# SCH_skymest-2026_06_07_2026-06-14.net
KiCad netlist of a schematic drawn in EasyEDA
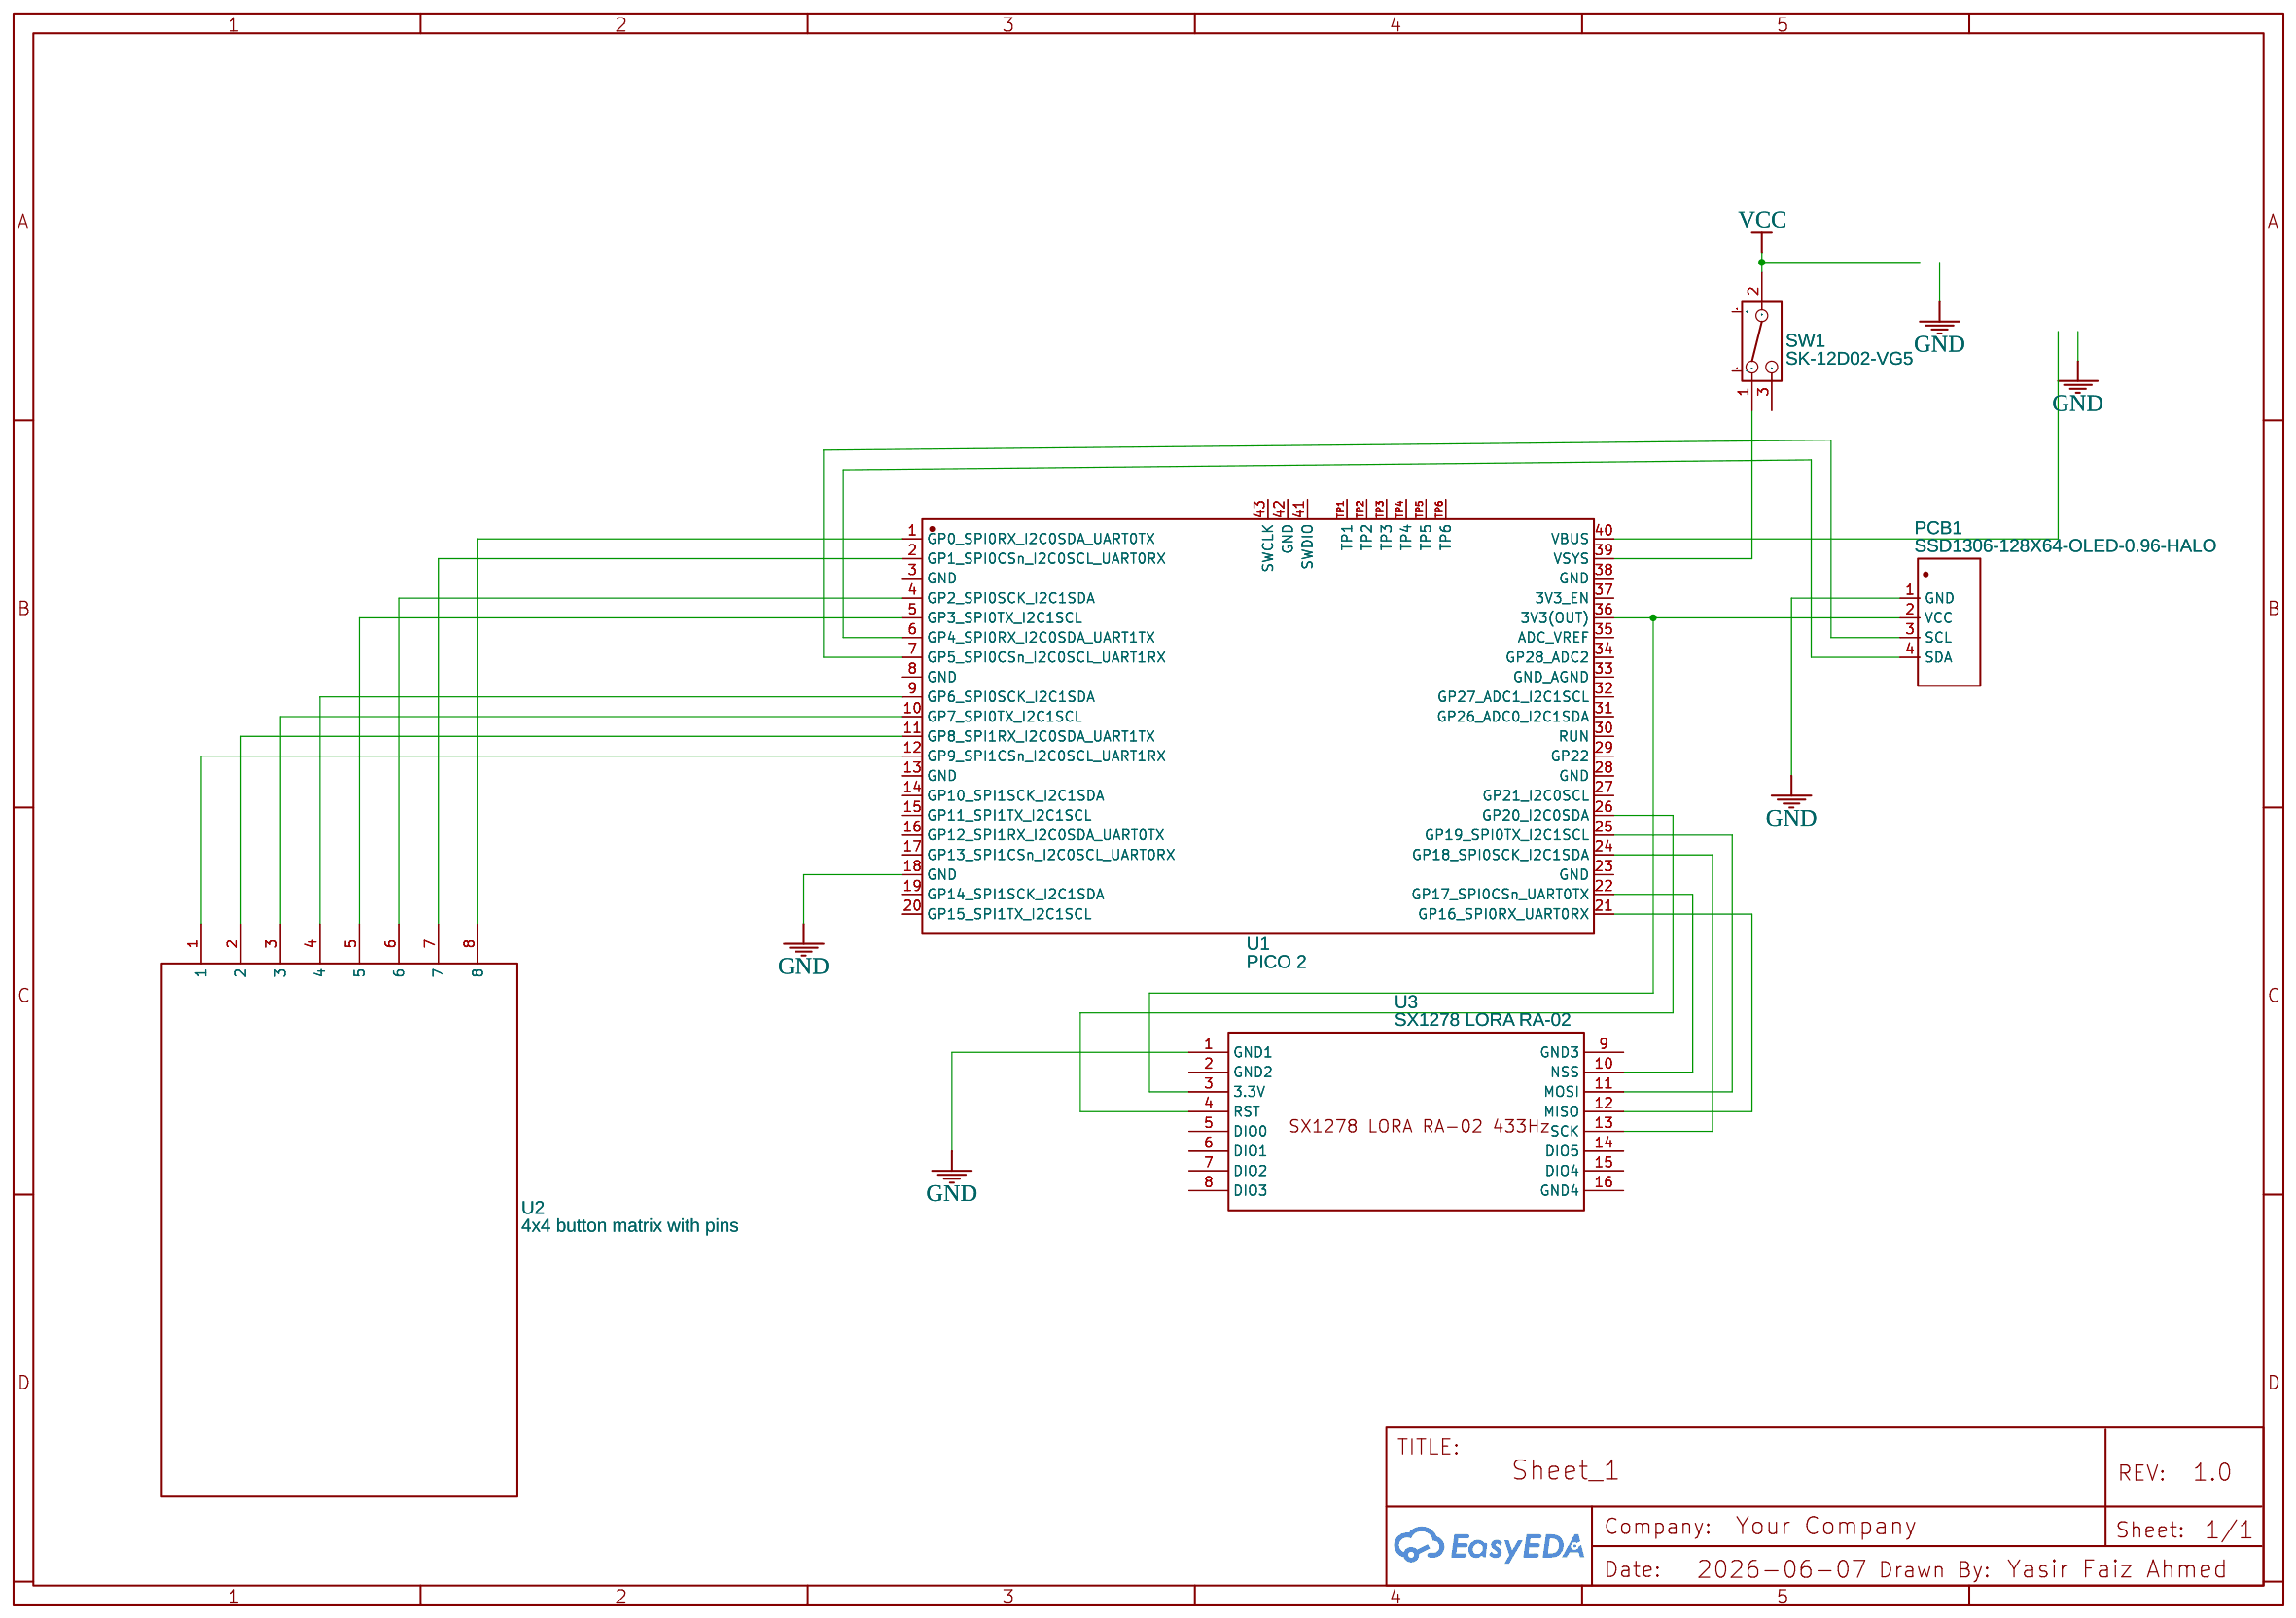
[diagram p0: schematic sheet]

(export (version "E")
  (design (tool "Eeschema 10.0.6"))
  (components
    (comp (ref "PCB1")
      (value "SSD1306-128X64-OLED-0.96-HALO")
      (libsource (lib "") (part "SSD1306-128X64-OLED-0.96-HALO"))
    )
    (comp (ref "SW1")
      (value "SK-12D02-VG5")
      (fields (field (name "Manufacturer") "Rectangular Connectors - Contacts"))
      (libsource (lib "") (part "SK-12D02-VG5"))
    )
    (comp (ref "U1")
      (value "PICO 2")
      (fields (field (name "Manufacturer Part") "Pico 2") (field (name "Manufacturer") "Raspberry Pi(树莓派)"))
      (libsource (lib "") (part "PICO 2"))
    )
    (comp (ref "U2")
      (value "4x4 button matrix with pins")
      (libsource (lib "") (part "4x4 button matrix with pins"))
    )
    (comp (ref "U3") (value "SX1278 LORA RA-02") (libsource (lib "") (part "SX1278 LORA RA-02")))
  )
  (nets
    (net (code "1") (name "GND") (class "Default")
      (node (ref "PCB1") (pin "1") (pinfunction "GND_1") (pintype "input"))
      (node (ref "U1") (pin "18") (pinfunction "GND_18") (pintype "unspecified"))
      (node (ref "U3") (pin "1") (pinfunction "GND1_1") (pintype "unspecified"))
    )
    (net (code "2") (name "Net-(PCB1-SCL)") (class "Default")
      (node (ref "PCB1") (pin "3") (pinfunction "SCL_3") (pintype "passive"))
      (node (ref "U1") (pin "7") (pinfunction "GP5_SPI0CSn_I2C0SCL_UART1RX_7") (pintype "unspecified"))
    )
    (net (code "3") (name "Net-(PCB1-SDA)") (class "Default")
      (node (ref "PCB1") (pin "4") (pinfunction "SDA_4") (pintype "passive"))
      (node (ref "U1") (pin "6") (pinfunction "GP4_SPI0RX_I2C0SDA_UART1TX_6") (pintype "unspecified"))
    )
    (net (code "4") (name "Net-(PCB1-VCC)") (class "Default")
      (node (ref "PCB1") (pin "2") (pinfunction "VCC_2") (pintype "input"))
      (node (ref "U1") (pin "36") (pinfunction "3V3(OUT)_36") (pintype "unspecified"))
      (node (ref "U3") (pin "3") (pinfunction "3.3V_3") (pintype "unspecified"))
    )
    (net (code "5") (name "Net-(U1-GP0_SPI0RX_I2C0SDA_UART0TX)") (class "Default")
      (node (ref "U1") (pin "1") (pinfunction "GP0_SPI0RX_I2C0SDA_UART0TX_1") (pintype "unspecified"))
      (node (ref "U2") (pin "8") (pinfunction "8_8") (pintype "unspecified"))
    )
    (net (code "6") (name "Net-(U1-GP1_SPI0CSn_I2C0SCL_UART0RX)") (class "Default")
      (node (ref "U1") (pin "2") (pinfunction "GP1_SPI0CSn_I2C0SCL_UART0RX_2") (pintype "unspecified"))
      (node (ref "U2") (pin "7") (pinfunction "7_7") (pintype "unspecified"))
    )
    (net (code "7") (name "Net-(U1-GP2_SPI0SCK_I2C1SDA)") (class "Default")
      (node (ref "U1") (pin "4") (pinfunction "GP2_SPI0SCK_I2C1SDA_4") (pintype "unspecified"))
      (node (ref "U2") (pin "6") (pinfunction "6_6") (pintype "unspecified"))
    )
    (net (code "8") (name "Net-(U1-GP3_SPI0TX_I2C1SCL)") (class "Default")
      (node (ref "U1") (pin "5") (pinfunction "GP3_SPI0TX_I2C1SCL_5") (pintype "unspecified"))
      (node (ref "U2") (pin "5") (pinfunction "5_5") (pintype "unspecified"))
    )
    (net (code "9") (name "Net-(U1-GP6_SPI0SCK_I2C1SDA)") (class "Default")
      (node (ref "U1") (pin "9") (pinfunction "GP6_SPI0SCK_I2C1SDA_9") (pintype "unspecified"))
      (node (ref "U2") (pin "4") (pinfunction "4_4") (pintype "unspecified"))
    )
    (net (code "10") (name "Net-(U1-GP7_SPI0TX_I2C1SCL)") (class "Default")
      (node (ref "U1") (pin "10") (pinfunction "GP7_SPI0TX_I2C1SCL_10") (pintype "unspecified"))
      (node (ref "U2") (pin "3") (pinfunction "3_3") (pintype "unspecified"))
    )
    (net (code "11") (name "Net-(U1-GP8_SPI1RX_I2C0SDA_UART1TX)") (class "Default")
      (node (ref "U1") (pin "11") (pinfunction "GP8_SPI1RX_I2C0SDA_UART1TX_11") (pintype "unspecified"))
      (node (ref "U2") (pin "2") (pinfunction "2_2") (pintype "unspecified"))
    )
    (net (code "12") (name "Net-(U1-GP9_SPI1CSn_I2C0SCL_UART1RX)") (class "Default")
      (node (ref "U1") (pin "12") (pinfunction "GP9_SPI1CSn_I2C0SCL_UART1RX_12") (pintype "unspecified"))
      (node (ref "U2") (pin "1") (pinfunction "1_1") (pintype "unspecified"))
    )
    (net (code "13") (name "Net-(U1-GP16_SPI0RX_UART0RX)") (class "Default")
      (node (ref "U1") (pin "21") (pinfunction "GP16_SPI0RX_UART0RX_21") (pintype "unspecified"))
      (node (ref "U3") (pin "12") (pinfunction "MISO_12") (pintype "unspecified"))
    )
    (net (code "14") (name "Net-(U1-GP17_SPI0CSn_UART0TX)") (class "Default")
      (node (ref "U1") (pin "22") (pinfunction "GP17_SPI0CSn_UART0TX_22") (pintype "unspecified"))
      (node (ref "U3") (pin "10") (pinfunction "NSS_10") (pintype "unspecified"))
    )
    (net (code "15") (name "Net-(U1-GP18_SPI0SCK_I2C1SDA)") (class "Default")
      (node (ref "U1") (pin "24") (pinfunction "GP18_SPI0SCK_I2C1SDA_24") (pintype "unspecified"))
      (node (ref "U3") (pin "13") (pinfunction "SCK_13") (pintype "unspecified"))
    )
    (net (code "16") (name "Net-(U1-GP19_SPI0TX_I2C1SCL)") (class "Default")
      (node (ref "U1") (pin "25") (pinfunction "GP19_SPI0TX_I2C1SCL_25") (pintype "unspecified"))
      (node (ref "U3") (pin "11") (pinfunction "MOSI_11") (pintype "unspecified"))
    )
    (net (code "17") (name "Net-(U1-GP20_I2C0SDA)") (class "Default")
      (node (ref "U1") (pin "26") (pinfunction "GP20_I2C0SDA_26") (pintype "unspecified"))
      (node (ref "U3") (pin "4") (pinfunction "RST_4") (pintype "unspecified"))
    )
    (net (code "18") (name "Net-(U1-VSYS)") (class "Default")
      (node (ref "SW1") (pin "1") (pinfunction "1_1") (pintype "unspecified"))
      (node (ref "U1") (pin "39") (pinfunction "VSYS_39") (pintype "unspecified"))
    )
    (net (code "19") (name "VCC") (class "Default")
      (node (ref "SW1") (pin "2") (pinfunction "2_2") (pintype "unspecified"))
    )
    (net (code "20") (name "unconnected-(SW1-Pad3)") (class "Default")
      (node (ref "SW1") (pin "3") (pinfunction "3_3") (pintype "unspecified"))
    )
    (net (code "21") (name "unconnected-(SW1-Pad4)") (class "Default")
      (node (ref "SW1") (pin "4") (pinfunction "4_4") (pintype "unspecified"))
    )
    (net (code "22") (name "unconnected-(SW1-Pad5)") (class "Default")
      (node (ref "SW1") (pin "5") (pinfunction "5_5") (pintype "unspecified"))
    )
    (net (code "23") (name "unconnected-(U1-3V3_EN-Pad37)") (class "Default")
      (node (ref "U1") (pin "37") (pinfunction "3V3_EN_37") (pintype "unspecified"))
    )
    (net (code "24") (name "unconnected-(U1-ADC_VREF-Pad35)") (class "Default")
      (node (ref "U1") (pin "35") (pinfunction "ADC_VREF_35") (pintype "unspecified"))
    )
    (net (code "25") (name "unconnected-(U1-GND-Pad3)") (class "Default")
      (node (ref "U1") (pin "3") (pinfunction "GND_3") (pintype "unspecified"))
    )
    (net (code "26") (name "unconnected-(U1-GND-Pad8)") (class "Default")
      (node (ref "U1") (pin "8") (pinfunction "GND_8") (pintype "unspecified"))
    )
    (net (code "27") (name "unconnected-(U1-GND-Pad13)") (class "Default")
      (node (ref "U1") (pin "13") (pinfunction "GND_13") (pintype "unspecified"))
    )
    (net (code "28") (name "unconnected-(U1-GND-Pad23)") (class "Default")
      (node (ref "U1") (pin "23") (pinfunction "GND_23") (pintype "unspecified"))
    )
    (net (code "29") (name "unconnected-(U1-GND-Pad28)") (class "Default")
      (node (ref "U1") (pin "28") (pinfunction "GND_28") (pintype "unspecified"))
    )
    (net (code "30") (name "unconnected-(U1-GND-Pad38)") (class "Default")
      (node (ref "U1") (pin "38") (pinfunction "GND_38") (pintype "unspecified"))
    )
    (net (code "31") (name "unconnected-(U1-GND-Pad42)") (class "Default")
      (node (ref "U1") (pin "42") (pinfunction "GND_42") (pintype "unspecified"))
    )
    (net (code "32") (name "unconnected-(U1-GND_AGND-Pad33)") (class "Default")
      (node (ref "U1") (pin "33") (pinfunction "GND_AGND_33") (pintype "unspecified"))
    )
    (net (code "33") (name "unconnected-(U1-GP10_SPI1SCK_I2C1SDA-Pad14)") (class "Default")
      (node (ref "U1") (pin "14") (pinfunction "GP10_SPI1SCK_I2C1SDA_14") (pintype "unspecified"))
    )
    (net (code "34") (name "unconnected-(U1-GP11_SPI1TX_I2C1SCL-Pad15)") (class "Default")
      (node (ref "U1") (pin "15") (pinfunction "GP11_SPI1TX_I2C1SCL_15") (pintype "unspecified"))
    )
    (net (code "35") (name "unconnected-(U1-GP12_SPI1RX_I2C0SDA_UART0TX-Pad16)") (class "Default")
      (node (ref "U1") (pin "16") (pinfunction "GP12_SPI1RX_I2C0SDA_UART0TX_16") (pintype "unspecified"))
    )
    (net (code "36") (name "unconnected-(U1-GP13_SPI1CSn_I2C0SCL_UART0RX-Pad17)") (class "Default")
      (node (ref "U1") (pin "17") (pinfunction "GP13_SPI1CSn_I2C0SCL_UART0RX_17") (pintype "unspecified"))
    )
    (net (code "37") (name "unconnected-(U1-GP14_SPI1SCK_I2C1SDA-Pad19)") (class "Default")
      (node (ref "U1") (pin "19") (pinfunction "GP14_SPI1SCK_I2C1SDA_19") (pintype "unspecified"))
    )
    (net (code "38") (name "unconnected-(U1-GP15_SPI1TX_I2C1SCL-Pad20)") (class "Default")
      (node (ref "U1") (pin "20") (pinfunction "GP15_SPI1TX_I2C1SCL_20") (pintype "unspecified"))
    )
    (net (code "39") (name "unconnected-(U1-GP21_I2C0SCL-Pad27)") (class "Default")
      (node (ref "U1") (pin "27") (pinfunction "GP21_I2C0SCL_27") (pintype "unspecified"))
    )
    (net (code "40") (name "unconnected-(U1-GP22-Pad29)") (class "Default")
      (node (ref "U1") (pin "29") (pinfunction "GP22_29") (pintype "unspecified"))
    )
    (net (code "41") (name "unconnected-(U1-GP26_ADC0_I2C1SDA-Pad31)") (class "Default")
      (node (ref "U1") (pin "31") (pinfunction "GP26_ADC0_I2C1SDA_31") (pintype "unspecified"))
    )
    (net (code "42") (name "unconnected-(U1-GP27_ADC1_I2C1SCL-Pad32)") (class "Default")
      (node (ref "U1") (pin "32") (pinfunction "GP27_ADC1_I2C1SCL_32") (pintype "unspecified"))
    )
    (net (code "43") (name "unconnected-(U1-GP28_ADC2-Pad34)") (class "Default")
      (node (ref "U1") (pin "34") (pinfunction "GP28_ADC2_34") (pintype "unspecified"))
    )
    (net (code "44") (name "unconnected-(U1-PadTP1)") (class "Default")
      (node (ref "U1") (pin "TP1") (pinfunction "TP1_TP1") (pintype "unspecified"))
    )
    (net (code "45") (name "unconnected-(U1-PadTP2)") (class "Default")
      (node (ref "U1") (pin "TP2") (pinfunction "TP2_TP2") (pintype "unspecified"))
    )
    (net (code "46") (name "unconnected-(U1-PadTP3)") (class "Default")
      (node (ref "U1") (pin "TP3") (pinfunction "TP3_TP3") (pintype "unspecified"))
    )
    (net (code "47") (name "unconnected-(U1-PadTP4)") (class "Default")
      (node (ref "U1") (pin "TP4") (pinfunction "TP4_TP4") (pintype "unspecified"))
    )
    (net (code "48") (name "unconnected-(U1-PadTP5)") (class "Default")
      (node (ref "U1") (pin "TP5") (pinfunction "TP5_TP5") (pintype "unspecified"))
    )
    (net (code "49") (name "unconnected-(U1-PadTP6)") (class "Default")
      (node (ref "U1") (pin "TP6") (pinfunction "TP6_TP6") (pintype "unspecified"))
    )
    (net (code "50") (name "unconnected-(U1-RUN-Pad30)") (class "Default")
      (node (ref "U1") (pin "30") (pinfunction "RUN_30") (pintype "unspecified"))
    )
    (net (code "51") (name "unconnected-(U1-SWCLK-Pad43)") (class "Default")
      (node (ref "U1") (pin "43") (pinfunction "SWCLK_43") (pintype "unspecified"))
    )
    (net (code "52") (name "unconnected-(U1-SWDIO-Pad41)") (class "Default")
      (node (ref "U1") (pin "41") (pinfunction "SWDIO_41") (pintype "unspecified"))
    )
    (net (code "53") (name "unconnected-(U1-VBUS-Pad40)") (class "Default")
      (node (ref "U1") (pin "40") (pinfunction "VBUS_40") (pintype "unspecified"))
    )
    (net (code "54") (name "unconnected-(U3-DIO0-Pad5)") (class "Default")
      (node (ref "U3") (pin "5") (pinfunction "DIO0_5") (pintype "unspecified"))
    )
    (net (code "55") (name "unconnected-(U3-DIO1-Pad6)") (class "Default")
      (node (ref "U3") (pin "6") (pinfunction "DIO1_6") (pintype "unspecified"))
    )
    (net (code "56") (name "unconnected-(U3-DIO2-Pad7)") (class "Default")
      (node (ref "U3") (pin "7") (pinfunction "DIO2_7") (pintype "unspecified"))
    )
    (net (code "57") (name "unconnected-(U3-DIO3-Pad8)") (class "Default")
      (node (ref "U3") (pin "8") (pinfunction "DIO3_8") (pintype "unspecified"))
    )
    (net (code "58") (name "unconnected-(U3-DIO4-Pad15)") (class "Default")
      (node (ref "U3") (pin "15") (pinfunction "DIO4_15") (pintype "unspecified"))
    )
    (net (code "59") (name "unconnected-(U3-DIO5-Pad14)") (class "Default")
      (node (ref "U3") (pin "14") (pinfunction "DIO5_14") (pintype "unspecified"))
    )
    (net (code "60") (name "unconnected-(U3-GND2-Pad2)") (class "Default")
      (node (ref "U3") (pin "2") (pinfunction "GND2_2") (pintype "unspecified"))
    )
    (net (code "61") (name "unconnected-(U3-GND3-Pad9)") (class "Default")
      (node (ref "U3") (pin "9") (pinfunction "GND3_9") (pintype "unspecified"))
    )
    (net (code "62") (name "unconnected-(U3-GND4-Pad16)") (class "Default")
      (node (ref "U3") (pin "16") (pinfunction "GND4_16") (pintype "unspecified"))
    )
  )
)
